# 2_4GBT.net
KiCad netlist of a schematic drawn in Altium Designer
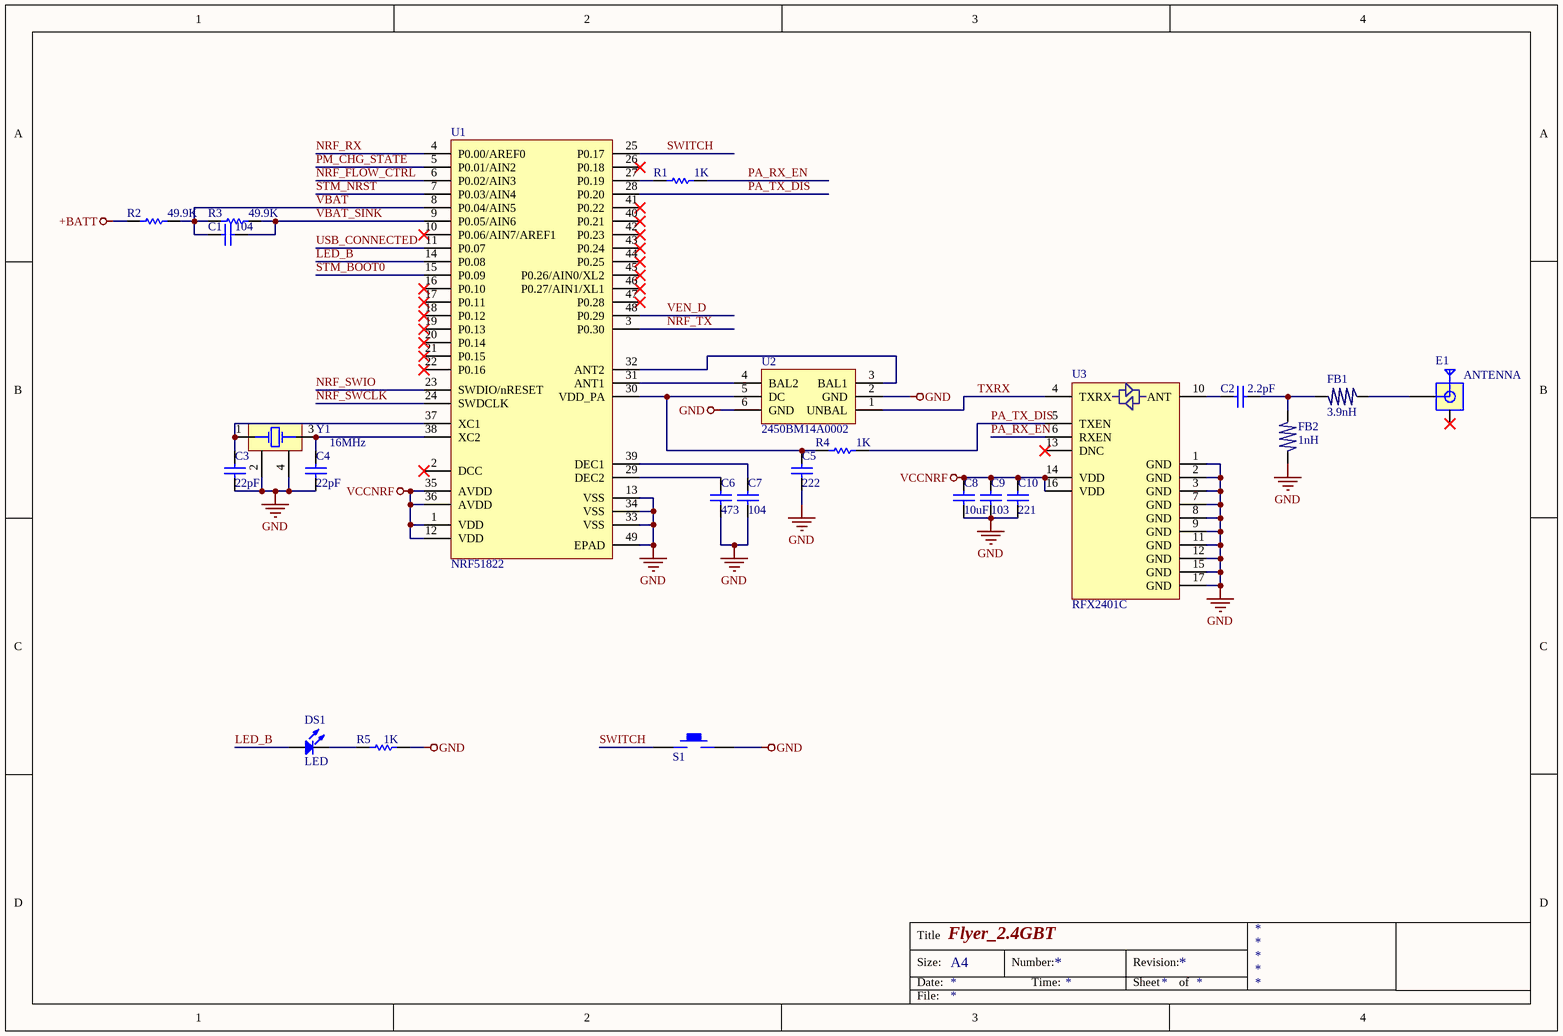
[diagram p0: 2.4GBT.SchDoc]

(export (version "E")
  (design (tool "Eeschema 10.0.6"))
  (components
    (comp (ref "C1")
      (value "104")
      (footprint "C0603")
      (description "电容")
      (fields (field (name "PUBLISHER") "Altium Limited"))
      (libsource (lib "Devices") (part "C0603"))
    )
    (comp (ref "C2")
      (value "2.2pF")
      (footprint "C0603")
      (description "电容")
      (fields (field (name "PUBLISHER") "Altium Limited"))
      (libsource (lib "Devices") (part "C0603"))
    )
    (comp (ref "C3")
      (value "22pF")
      (footprint "C0603")
      (description "电容")
      (fields (field (name "PUBLISHER") "Altium Limited"))
      (libsource (lib "Devices") (part "C0603"))
    )
    (comp (ref "C4")
      (value "22pF")
      (footprint "C0603")
      (description "电容")
      (fields (field (name "PUBLISHER") "Altium Limited"))
      (libsource (lib "Devices") (part "C0603"))
    )
    (comp (ref "C5")
      (value "222")
      (footprint "C0603")
      (description "电容")
      (fields (field (name "PUBLISHER") "Altium Limited"))
      (libsource (lib "Devices") (part "C0603"))
    )
    (comp (ref "C6")
      (value "473")
      (footprint "C0603")
      (description "电容")
      (fields (field (name "PUBLISHER") "Altium Limited"))
      (libsource (lib "Devices") (part "C0603"))
    )
    (comp (ref "C7")
      (value "104")
      (footprint "C0603")
      (description "电容")
      (fields (field (name "PUBLISHER") "Altium Limited"))
      (libsource (lib "Devices") (part "C0603"))
    )
    (comp (ref "C8")
      (value "10uF")
      (footprint "C0603")
      (description "电容")
      (fields (field (name "PUBLISHER") "Altium Limited"))
      (libsource (lib "Devices") (part "C0603"))
    )
    (comp (ref "C9")
      (value "103")
      (footprint "C0603")
      (description "电容")
      (fields (field (name "PUBLISHER") "Altium Limited"))
      (libsource (lib "Devices") (part "C0603"))
    )
    (comp (ref "C10")
      (value "221")
      (footprint "C0603")
      (description "电容")
      (fields (field (name "PUBLISHER") "Altium Limited"))
      (libsource (lib "Devices") (part "C0603"))
    )
    (comp (ref "DS1")
      (value "LED")
      (footprint "LED-2-1206")
      (description "Typical RED, GREEN, YELLOW, AMBER GaAs LED")
      (fields (field (name "PUBLISHER") "Altium Limited"))
      (libsource (lib "Devices") (part "LED"))
    )
    (comp (ref "E1") (value "ANTENNA") (footprint "AN3216") (libsource (lib "Devices") (part "ANTENNA")))
    (comp (ref "FB1")
      (value "3.9nH")
      (footprint "L0603")
      (description "磁珠")
      (libsource (lib "Devices") (part "L-Beads"))
    )
    (comp (ref "FB2")
      (value "1nH")
      (footprint "L0603")
      (description "磁珠")
      (libsource (lib "") (part "L-Beads_1"))
    )
    (comp (ref "R1")
      (value "1K")
      (footprint "R0603")
      (description "电阻")
      (fields (field (name "PUBLISHER") "Altium Limited"))
      (libsource (lib "Devices") (part "RES0603"))
    )
    (comp (ref "R2")
      (value "49.9K")
      (footprint "R0603")
      (description "电阻")
      (fields (field (name "PUBLISHER") "Altium Limited"))
      (libsource (lib "Devices") (part "RES0603"))
    )
    (comp (ref "R3")
      (value "49.9K")
      (footprint "R0603")
      (description "电阻")
      (fields (field (name "PUBLISHER") "Altium Limited"))
      (libsource (lib "Devices") (part "RES0603"))
    )
    (comp (ref "R4")
      (value "1K")
      (footprint "R0603")
      (description "电阻")
      (fields (field (name "PUBLISHER") "Altium Limited"))
      (libsource (lib "Devices") (part "RES0603"))
    )
    (comp (ref "R5")
      (value "1K")
      (footprint "R0603")
      (description "电阻")
      (fields (field (name "PUBLISHER") "Altium Limited"))
      (libsource (lib "Devices") (part "RES0603"))
    )
    (comp (ref "S1")
      (value "KEY")
      (footprint "KEY-3X6X3.5-C")
      (description "普通轻触按钮")
      (libsource (lib "Devices") (part "KEY"))
    )
    (comp (ref "U1") (value "NRF51822") (footprint "QFN-48") (libsource (lib "IC") (part "NRF51822")))
    (comp (ref "U2") (value "2450BM14A0002") (footprint "0603-6") (libsource (lib "IC") (part "BALUN")))
    (comp (ref "U3") (value "RFX2401C") (footprint "QFN-16") (libsource (lib "IC") (part "RFX2401C")))
    (comp (ref "Y1")
      (value "16MHz")
      (footprint "X-TSX-3225")
      (description "Crystal Oscillator")
      (fields (field (name "PUBLISHER") "Altium Limited"))
      (libsource (lib "Devices") (part "XTAL_1"))
    )
  )
  (nets
    (net (code "1") (name "+BATT") (class "Default")
      (node (ref "R2") (pin "1") (pinfunction "1_1") (pintype "passive"))
    )
    (net (code "2") (name "/LED_B") (class "Default")
      (node (ref "DS1") (pin "1") (pinfunction "A_1") (pintype "passive"))
      (node (ref "U1") (pin "14") (pinfunction "P0.08_14") (pintype "passive"))
    )
    (net (code "3") (name "/NRF_FLOW_CTRL") (class "Default")
      (node (ref "U1") (pin "6") (pinfunction "P0.02/AIN3_6") (pintype "passive"))
    )
    (net (code "4") (name "/NRF_RX") (class "Default")
      (node (ref "U1") (pin "4") (pinfunction "P0.00/AREF0_4") (pintype "passive"))
    )
    (net (code "5") (name "/NRF_SWCLK") (class "Default")
      (node (ref "U1") (pin "24") (pinfunction "SWDCLK_24") (pintype "passive"))
    )
    (net (code "6") (name "/NRF_SWIO") (class "Default")
      (node (ref "U1") (pin "23") (pinfunction "SWDIO/nRESET_23") (pintype "passive"))
    )
    (net (code "7") (name "/NRF_TX") (class "Default")
      (node (ref "U1") (pin "3") (pinfunction "P0.30_3") (pintype "passive"))
    )
    (net (code "8") (name "/PA_RX_EN") (class "Default")
      (node (ref "R1") (pin "2") (pinfunction "2_2") (pintype "passive"))
      (node (ref "U3") (pin "6") (pinfunction "RXEN_6") (pintype "passive"))
    )
    (net (code "9") (name "/PA_TX_DIS") (class "Default")
      (node (ref "R4") (pin "2") (pinfunction "2_2") (pintype "passive"))
      (node (ref "U1") (pin "28") (pinfunction "P0.20_28") (pintype "passive"))
      (node (ref "U3") (pin "5") (pinfunction "TXEN_5") (pintype "passive"))
    )
    (net (code "10") (name "/PM_CHG_STATE") (class "Default")
      (node (ref "U1") (pin "5") (pinfunction "P0.01/AIN2_5") (pintype "passive"))
    )
    (net (code "11") (name "/STM_BOOT0") (class "Default")
      (node (ref "U1") (pin "15") (pinfunction "P0.09_15") (pintype "passive"))
    )
    (net (code "12") (name "/STM_NRST") (class "Default")
      (node (ref "U1") (pin "7") (pinfunction "P0.03/AIN4_7") (pintype "passive"))
    )
    (net (code "13") (name "/SWITCH") (class "Default")
      (node (ref "S1") (pin "1") (pinfunction "1_1") (pintype "passive"))
      (node (ref "U1") (pin "25") (pinfunction "P0.17_25") (pintype "passive"))
    )
    (net (code "14") (name "/TXRX") (class "Default")
      (node (ref "U2") (pin "1") (pinfunction "UNBAL_1") (pintype "passive"))
      (node (ref "U3") (pin "4") (pinfunction "TXRX_4") (pintype "passive"))
    )
    (net (code "15") (name "/USB_CONNECTED") (class "Default")
      (node (ref "U1") (pin "11") (pinfunction "P0.07_11") (pintype "passive"))
    )
    (net (code "16") (name "/VBAT") (class "Default")
      (node (ref "C1") (pin "2") (pinfunction "2_2") (pintype "passive"))
      (node (ref "R2") (pin "2") (pinfunction "2_2") (pintype "passive"))
      (node (ref "R3") (pin "1") (pinfunction "1_1") (pintype "passive"))
      (node (ref "U1") (pin "8") (pinfunction "P0.04/AIN5_8") (pintype "passive"))
    )
    (net (code "17") (name "/VBAT_SINK") (class "Default")
      (node (ref "C1") (pin "1") (pinfunction "1_1") (pintype "passive"))
      (node (ref "R3") (pin "2") (pinfunction "2_2") (pintype "passive"))
      (node (ref "U1") (pin "9") (pinfunction "P0.05/AIN6_9") (pintype "passive"))
    )
    (net (code "18") (name "/VEN_D") (class "Default")
      (node (ref "U1") (pin "48") (pinfunction "P0.29_48") (pintype "passive"))
    )
    (net (code "19") (name "GND") (class "Default")
      (node (ref "C10") (pin "1") (pinfunction "1_1") (pintype "passive"))
      (node (ref "C3") (pin "1") (pinfunction "1_1") (pintype "passive"))
      (node (ref "C4") (pin "1") (pinfunction "1_1") (pintype "passive"))
      (node (ref "C5") (pin "1") (pinfunction "1_1") (pintype "passive"))
      (node (ref "C6") (pin "1") (pinfunction "1_1") (pintype "passive"))
      (node (ref "C7") (pin "1") (pinfunction "1_1") (pintype "passive"))
      (node (ref "C8") (pin "1") (pinfunction "1_1") (pintype "passive"))
      (node (ref "C9") (pin "1") (pinfunction "1_1") (pintype "passive"))
      (node (ref "FB2") (pin "2") (pintype "passive"))
      (node (ref "R5") (pin "1") (pinfunction "1_1") (pintype "passive"))
      (node (ref "S1") (pin "2") (pinfunction "2_2") (pintype "passive"))
      (node (ref "U1") (pin "13") (pinfunction "VSS_13") (pintype "passive"))
      (node (ref "U1") (pin "33") (pinfunction "VSS_33") (pintype "passive"))
      (node (ref "U1") (pin "34") (pinfunction "VSS_34") (pintype "passive"))
      (node (ref "U1") (pin "49") (pinfunction "EPAD_49") (pintype "passive"))
      (node (ref "U2") (pin "2") (pinfunction "GND_2") (pintype "passive"))
      (node (ref "U2") (pin "6") (pinfunction "GND_6") (pintype "passive"))
      (node (ref "U3") (pin "1") (pinfunction "GND_1") (pintype "passive"))
      (node (ref "U3") (pin "11") (pinfunction "GND_11") (pintype "passive"))
      (node (ref "U3") (pin "12") (pinfunction "GND_12") (pintype "passive"))
      (node (ref "U3") (pin "15") (pinfunction "GND_15") (pintype "passive"))
      (node (ref "U3") (pin "17") (pinfunction "GND_17") (pintype "passive"))
      (node (ref "U3") (pin "2") (pinfunction "GND_2") (pintype "passive"))
      (node (ref "U3") (pin "3") (pinfunction "GND_3") (pintype "passive"))
      (node (ref "U3") (pin "7") (pinfunction "GND_7") (pintype "passive"))
      (node (ref "U3") (pin "8") (pinfunction "GND_8") (pintype "passive"))
      (node (ref "U3") (pin "9") (pinfunction "GND_9") (pintype "passive"))
      (node (ref "Y1") (pin "2") (pinfunction "2_2") (pintype "passive"))
      (node (ref "Y1") (pin "4") (pinfunction "4_4") (pintype "passive"))
    )
    (net (code "20") (name "Net-(C2-Pad1)") (class "Default")
      (node (ref "C2") (pin "1") (pinfunction "1_1") (pintype "passive"))
      (node (ref "FB1") (pin "2") (pintype "passive"))
      (node (ref "FB2") (pin "1") (pintype "passive"))
    )
    (net (code "21") (name "Net-(DS1-K)") (class "Default")
      (node (ref "DS1") (pin "2") (pinfunction "K_2") (pintype "passive"))
      (node (ref "R5") (pin "2") (pinfunction "2_2") (pintype "passive"))
    )
    (net (code "22") (name "Net-(E1-Pad1)") (class "Default")
      (node (ref "E1") (pin "1") (pinfunction "1_1") (pintype "passive"))
      (node (ref "FB1") (pin "1") (pintype "passive"))
    )
    (net (code "23") (name "Net-(U1-ANT1)") (class "Default")
      (node (ref "U1") (pin "31") (pinfunction "ANT1_31") (pintype "passive"))
      (node (ref "U2") (pin "4") (pinfunction "BAL2_4") (pintype "passive"))
    )
    (net (code "24") (name "Net-(U1-ANT2)") (class "Default")
      (node (ref "U1") (pin "32") (pinfunction "ANT2_32") (pintype "passive"))
      (node (ref "U2") (pin "3") (pinfunction "BAL1_3") (pintype "passive"))
    )
    (net (code "25") (name "Net-(U1-DEC1)") (class "Default")
      (node (ref "C7") (pin "2") (pinfunction "2_2") (pintype "passive"))
      (node (ref "U1") (pin "39") (pinfunction "DEC1_39") (pintype "passive"))
    )
    (net (code "26") (name "Net-(U1-DEC2)") (class "Default")
      (node (ref "C6") (pin "2") (pinfunction "2_2") (pintype "passive"))
      (node (ref "U1") (pin "29") (pinfunction "DEC2_29") (pintype "passive"))
    )
    (net (code "27") (name "Net-(U1-P0.19)") (class "Default")
      (node (ref "R1") (pin "1") (pinfunction "1_1") (pintype "passive"))
      (node (ref "U1") (pin "27") (pinfunction "P0.19_27") (pintype "passive"))
    )
    (net (code "28") (name "Net-(U1-VDD_PA)") (class "Default")
      (node (ref "C5") (pin "2") (pinfunction "2_2") (pintype "passive"))
      (node (ref "R4") (pin "1") (pinfunction "1_1") (pintype "passive"))
      (node (ref "U1") (pin "30") (pinfunction "VDD_PA_30") (pintype "passive"))
      (node (ref "U2") (pin "5") (pinfunction "DC_5") (pintype "passive"))
    )
    (net (code "29") (name "Net-(U1-XC1)") (class "Default")
      (node (ref "C3") (pin "2") (pinfunction "2_2") (pintype "passive"))
      (node (ref "U1") (pin "37") (pinfunction "XC1_37") (pintype "passive"))
      (node (ref "Y1") (pin "1") (pinfunction "1_1") (pintype "passive"))
    )
    (net (code "30") (name "Net-(U1-XC2)") (class "Default")
      (node (ref "C4") (pin "2") (pinfunction "2_2") (pintype "passive"))
      (node (ref "U1") (pin "38") (pinfunction "XC2_38") (pintype "passive"))
      (node (ref "Y1") (pin "3") (pinfunction "3_3") (pintype "passive"))
    )
    (net (code "31") (name "Net-(U3-ANT)") (class "Default")
      (node (ref "C2") (pin "2") (pinfunction "2_2") (pintype "passive"))
      (node (ref "U3") (pin "10") (pinfunction "ANT_10") (pintype "passive"))
    )
    (net (code "32") (name "VCCNRF") (class "Default")
      (node (ref "C10") (pin "2") (pinfunction "2_2") (pintype "passive"))
      (node (ref "C8") (pin "2") (pinfunction "2_2") (pintype "passive"))
      (node (ref "C9") (pin "2") (pinfunction "2_2") (pintype "passive"))
      (node (ref "U1") (pin "1") (pinfunction "VDD_1") (pintype "passive"))
      (node (ref "U1") (pin "12") (pinfunction "VDD_12") (pintype "passive"))
      (node (ref "U1") (pin "35") (pinfunction "AVDD_35") (pintype "passive"))
      (node (ref "U1") (pin "36") (pinfunction "AVDD_36") (pintype "passive"))
      (node (ref "U3") (pin "14") (pinfunction "VDD_14") (pintype "passive"))
      (node (ref "U3") (pin "16") (pinfunction "VDD_16") (pintype "passive"))
    )
    (net (code "33") (name "unconnected-(E1-Pad2)") (class "Default")
      (node (ref "E1") (pin "2") (pinfunction "2_2") (pintype "power_in+no_connect"))
    )
    (net (code "34") (name "unconnected-(U1-DCC-Pad2)") (class "Default")
      (node (ref "U1") (pin "2") (pinfunction "DCC_2") (pintype "passive+no_connect"))
    )
    (net (code "35") (name "unconnected-(U1-P0.06{slash}AIN7{slash}AREF1-Pad10)") (class "Default")
      (node (ref "U1") (pin "10") (pinfunction "P0.06/AIN7/AREF1_10") (pintype "passive+no_connect"))
    )
    (net (code "36") (name "unconnected-(U1-P0.10-Pad16)") (class "Default")
      (node (ref "U1") (pin "16") (pinfunction "P0.10_16") (pintype "passive+no_connect"))
    )
    (net (code "37") (name "unconnected-(U1-P0.11-Pad17)") (class "Default")
      (node (ref "U1") (pin "17") (pinfunction "P0.11_17") (pintype "passive+no_connect"))
    )
    (net (code "38") (name "unconnected-(U1-P0.12-Pad18)") (class "Default")
      (node (ref "U1") (pin "18") (pinfunction "P0.12_18") (pintype "passive+no_connect"))
    )
    (net (code "39") (name "unconnected-(U1-P0.13-Pad19)") (class "Default")
      (node (ref "U1") (pin "19") (pinfunction "P0.13_19") (pintype "passive+no_connect"))
    )
    (net (code "40") (name "unconnected-(U1-P0.14-Pad20)") (class "Default")
      (node (ref "U1") (pin "20") (pinfunction "P0.14_20") (pintype "passive+no_connect"))
    )
    (net (code "41") (name "unconnected-(U1-P0.15-Pad21)") (class "Default")
      (node (ref "U1") (pin "21") (pinfunction "P0.15_21") (pintype "passive+no_connect"))
    )
    (net (code "42") (name "unconnected-(U1-P0.16-Pad22)") (class "Default")
      (node (ref "U1") (pin "22") (pinfunction "P0.16_22") (pintype "passive+no_connect"))
    )
    (net (code "43") (name "unconnected-(U1-P0.18-Pad26)") (class "Default")
      (node (ref "U1") (pin "26") (pinfunction "P0.18_26") (pintype "passive+no_connect"))
    )
    (net (code "44") (name "unconnected-(U1-P0.21-Pad40)") (class "Default")
      (node (ref "U1") (pin "40") (pinfunction "P0.21_40") (pintype "passive+no_connect"))
    )
    (net (code "45") (name "unconnected-(U1-P0.22-Pad41)") (class "Default")
      (node (ref "U1") (pin "41") (pinfunction "P0.22_41") (pintype "passive+no_connect"))
    )
    (net (code "46") (name "unconnected-(U1-P0.23-Pad42)") (class "Default")
      (node (ref "U1") (pin "42") (pinfunction "P0.23_42") (pintype "passive+no_connect"))
    )
    (net (code "47") (name "unconnected-(U1-P0.24-Pad43)") (class "Default")
      (node (ref "U1") (pin "43") (pinfunction "P0.24_43") (pintype "passive+no_connect"))
    )
    (net (code "48") (name "unconnected-(U1-P0.25-Pad44)") (class "Default")
      (node (ref "U1") (pin "44") (pinfunction "P0.25_44") (pintype "passive+no_connect"))
    )
    (net (code "49") (name "unconnected-(U1-P0.26{slash}AIN0{slash}XL2-Pad45)") (class "Default")
      (node (ref "U1") (pin "45") (pinfunction "P0.26/AIN0/XL2_45") (pintype "passive+no_connect"))
    )
    (net (code "50") (name "unconnected-(U1-P0.27{slash}AIN1{slash}XL1-Pad46)") (class "Default")
      (node (ref "U1") (pin "46") (pinfunction "P0.27/AIN1/XL1_46") (pintype "passive+no_connect"))
    )
    (net (code "51") (name "unconnected-(U1-P0.28-Pad47)") (class "Default")
      (node (ref "U1") (pin "47") (pinfunction "P0.28_47") (pintype "passive+no_connect"))
    )
    (net (code "52") (name "unconnected-(U3-DNC-Pad13)") (class "Default")
      (node (ref "U3") (pin "13") (pinfunction "DNC_13") (pintype "passive+no_connect"))
    )
  )
)
